# USB.net
KiCad netlist of a schematic drawn in Altium Designer
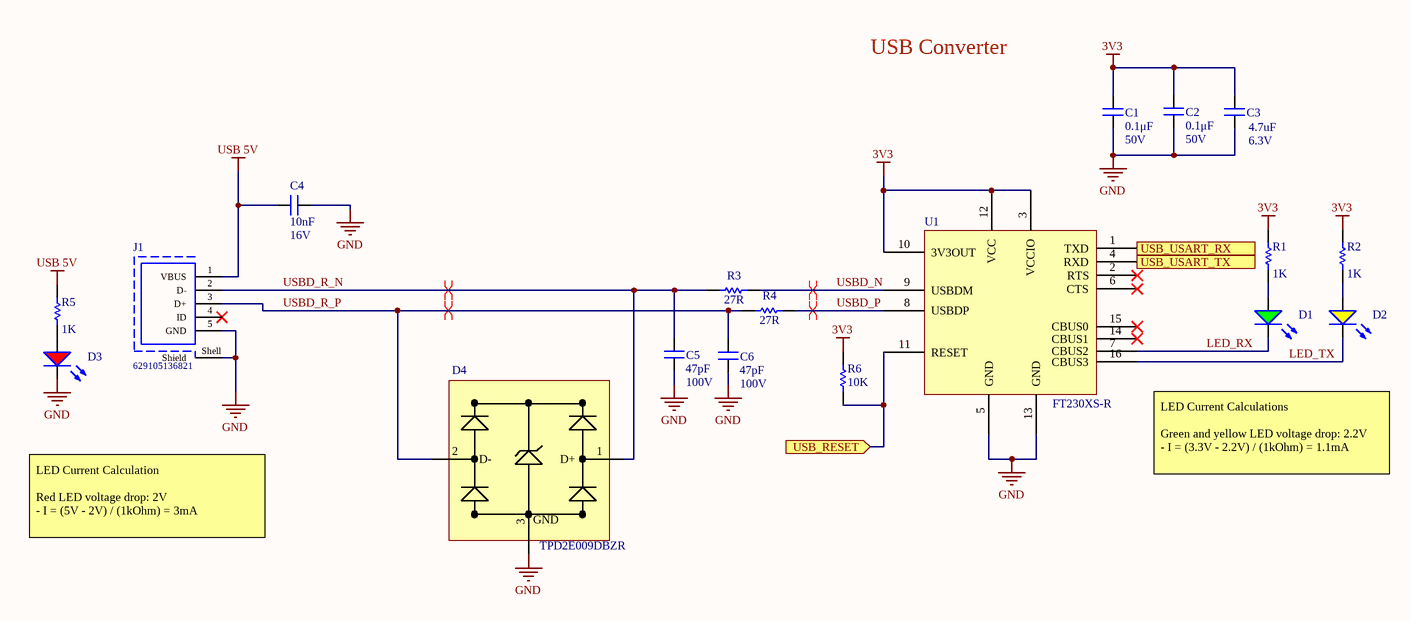
[diagram p0: USB.SchDoc]

(export (version "E")
  (design (tool "Eeschema 10.0.6"))
  (components
    (comp (ref "C1")
      (value "0.1μF")
      (footprint "CAP2012")
      (description "CAP CER 0.1UF 50V X7R 0805")
      (fields
        (field (name "TOLERANCE") "10%")
        (field (name "VOLTAGE RATING") "50V")
        (field (name "Comment") "CAP_0.1uF_50V_0805")
      )
      (libsource (lib "UWRT_Schematic_Library_2020") (part "CAP_0.1uF_50V_0805"))
    )
    (comp (ref "C2")
      (value "0.1μF")
      (footprint "CAP2012")
      (description "CAP CER 0.1UF 50V X7R 0805")
      (fields
        (field (name "TOLERANCE") "10%")
        (field (name "VOLTAGE RATING") "50V")
        (field (name "Comment") "CAP_0.1uF_50V_0805")
      )
      (libsource (lib "UWRT_Schematic_Library_2020") (part "CAP_0.1uF_50V_0805"))
    )
    (comp (ref "C3")
      (value "4.7uF")
      (footprint "CAPC0603(1608)55_N")
      (description "CAP CER 4.7UF 6.3V X5R 0603")
      (fields (field (name "VOLTAGE RATING") "6.3V") (field (name "Comment") "CAP_4.7uF_0603"))
      (libsource (lib "UWRT_Schematic_Library_2020") (part "CAP_4.7uF_0603"))
    )
    (comp (ref "C4")
      (value "10nF")
      (footprint "CAP0603")
      (description "CAP CER 10000PF 16V X7R 0603")
      (fields (field (name "VOLTAGE RATING") "16V") (field (name "Comment") "CAP_10nF_0603"))
      (libsource (lib "UWRT_Schematic_Library_2020") (part "CAP_10nF_0603"))
    )
    (comp (ref "C5")
      (value "47pF")
      (footprint "CAP0603")
      (description "CAP CER 47PF 100V C0G/NP0 0603")
      (fields (field (name "VOLTAGE RATING") "100V") (field (name "Comment") "CAP_47pF_100V_0603"))
      (libsource (lib "UWRT_Schematic_Library_2020") (part "CAP_47pF_100V_0603"))
    )
    (comp (ref "C6")
      (value "47pF")
      (footprint "CAP0603")
      (description "CAP CER 47PF 100V C0G/NP0 0603")
      (fields (field (name "VOLTAGE RATING") "100V") (field (name "Comment") "CAP_47pF_100V_0603"))
      (libsource (lib "UWRT_Schematic_Library_2020") (part "CAP_47pF_100V_0603"))
    )
    (comp (ref "D1")
      (value "LG R971-KN-1")
      (footprint "LED_0805_GREEN")
      (description "LED GREEN DIFFUSED 0805 SMD")
      (libsource (lib "UWRT_Schematic_Library_2020") (part "DIO_LED_G"))
    )
    (comp (ref "D2")
      (value "LY R976-PS-36")
      (footprint "LED_0805_YELLOW")
      (description "LED YELLOW DIFFUSED 0805 SMD")
      (libsource (lib "UWRT_Schematic_Library_2020") (part "DIO_LED_Y"))
    )
    (comp (ref "D3")
      (value "LS R976-NR-1")
      (footprint "LED_0805_RED")
      (description "LED RED DIFFUSED 0805 SMD")
      (libsource (lib "UWRT_Schematic_Library_2020") (part "DIO_LED_R"))
    )
    (comp (ref "D4")
      (value "TVS_DIODE_USB_5.5V")
      (footprint "SOT23-3")
      (description "TVS DIODE 5.5V 8V SOT23-3")
      (fields
        (field (name "MANUFACTURER") "Texas Instruments")
        (field (name "MANUFACTURER PART NUMBER") "TPD2E009DBZR")
      )
      (libsource (lib "UWRT_Schematic_Library_2020") (part "TVS_DIODE_USB_5.5V"))
    )
    (comp (ref "J1")
      (value "629105136821")
      (footprint "629105136821")
      (description "CONN RCPT USB2.0 MICRO B SMD R/A")
      (fields (field (name "MANUFACTURER") "Wurth Elektronik") (field (name "PUBLISHER") "WurthElektronik"))
      (libsource (lib "UWRT_Schematic_Library_2020") (part "WE 629105136821"))
    )
    (comp (ref "R1")
      (value "1K")
      (footprint "RESC0603(1608)_N")
      (description "RES SMD 1K OHM 5% 1/10W 0603")
      (fields (field (name "TOLERANCE") "5%") (field (name "Comment") "RES_1K_0603"))
      (libsource (lib "UWRT_Schematic_Library_2020") (part "RES_1K_0603"))
    )
    (comp (ref "R2")
      (value "1K")
      (footprint "RESC0603(1608)_N")
      (description "RES SMD 1K OHM 5% 1/10W 0603")
      (fields (field (name "TOLERANCE") "5%") (field (name "Comment") "RES_1K_0603"))
      (libsource (lib "UWRT_Schematic_Library_2020") (part "RES_1K_0603"))
    )
    (comp (ref "R3")
      (value "RES_27R_0603")
      (footprint "RESC0603(1608)_N")
      (description "RES SMD 27 OHM 5% 1/10W 0603")
      (fields
        (field (name "MANUFACTURER") "Yageo")
        (field (name "MANUFACTURER PART NUMBER") "RC0603JR-0727RL")
        (field (name "RESISTANCE") "27R")
      )
      (libsource (lib "UWRT_Schematic_Library_2020") (part "RES_27R_0603"))
    )
    (comp (ref "R4")
      (value "RES_27R_0603")
      (footprint "RESC0603(1608)_N")
      (description "RES SMD 27 OHM 5% 1/10W 0603")
      (fields
        (field (name "MANUFACTURER") "Yageo")
        (field (name "MANUFACTURER PART NUMBER") "RC0603JR-0727RL")
        (field (name "RESISTANCE") "27R")
      )
      (libsource (lib "UWRT_Schematic_Library_2020") (part "RES_27R_0603"))
    )
    (comp (ref "R5")
      (value "1K")
      (footprint "RESC0603(1608)_N")
      (description "RES SMD 1K OHM 5% 1/10W 0603")
      (fields (field (name "TOLERANCE") "5%") (field (name "Comment") "RES_1K_0603"))
      (libsource (lib "UWRT_Schematic_Library_2020") (part "RES_1K_0603"))
    )
    (comp (ref "R6")
      (value "10K")
      (footprint "RESC0603(1608)_N")
      (description "RES SMD 10K OHM 5% 1/10W 0603")
      (fields (field (name "TOLERANCE") "5%") (field (name "Comment") "RES_10K_0603"))
      (libsource (lib "UWRT_Schematic_Library_2020") (part "RES_10K_0603"))
    )
    (comp (ref "U1")
      (value "IC_USB_TRANSCEIVER")
      (footprint "SSOP16-0.635-5X4MM")
      (description "IC USB SERIAL BASIC UART 16SSOP")
      (fields (field (name "MANUFACTURER PART NUMBER 1") "FT230XS-R"))
      (libsource (lib "UWRT_Schematic_Library_2020") (part "IC_USB_TRANSCEIVER"))
    )
  )
  (nets
    (net (code "1") (name "/LED_RX") (class "Default")
      (node (ref "D1") (pin "2") (pinfunction "K_2") (pintype "passive"))
      (node (ref "U1") (pin "7") (pinfunction "CBUS2_7") (pintype "passive"))
    )
    (net (code "2") (name "/LED_TX") (class "Default")
      (node (ref "D2") (pin "2") (pinfunction "K_2") (pintype "passive"))
      (node (ref "U1") (pin "16") (pinfunction "CBUS3_16") (pintype "passive"))
    )
    (net (code "3") (name "/USBD_N") (class "Default")
      (node (ref "R3") (pin "2") (pinfunction "2_2") (pintype "passive"))
      (node (ref "U1") (pin "9") (pinfunction "USBDM_9") (pintype "passive"))
    )
    (net (code "4") (name "/USBD_P") (class "Default")
      (node (ref "R4") (pin "2") (pinfunction "2_2") (pintype "passive"))
      (node (ref "U1") (pin "8") (pinfunction "USBDP_8") (pintype "passive"))
    )
    (net (code "5") (name "/USBD_R_N") (class "Default")
      (node (ref "C5") (pin "2") (pinfunction "2_2") (pintype "passive"))
      (node (ref "D4") (pin "1") (pinfunction "D+_1") (pintype "passive"))
      (node (ref "J1") (pin "2") (pinfunction "D-_2") (pintype "passive"))
      (node (ref "R3") (pin "1") (pinfunction "1_1") (pintype "passive"))
    )
    (net (code "6") (name "/USBD_R_P") (class "Default")
      (node (ref "C6") (pin "1") (pinfunction "1_1") (pintype "passive"))
      (node (ref "D4") (pin "2") (pinfunction "D-_2") (pintype "passive"))
      (node (ref "J1") (pin "3") (pinfunction "D+_3") (pintype "passive"))
      (node (ref "R4") (pin "1") (pinfunction "1_1") (pintype "passive"))
    )
    (net (code "7") (name "/USB_RESET") (class "Default")
      (node (ref "R6") (pin "1") (pinfunction "1_1") (pintype "passive"))
      (node (ref "U1") (pin "11") (pinfunction "RESET_11") (pintype "passive"))
    )
    (net (code "8") (name "/USB_USART_RX") (class "Default")
      (node (ref "U1") (pin "1") (pinfunction "TXD_1") (pintype "passive"))
    )
    (net (code "9") (name "/USB_USART_TX") (class "Default")
      (node (ref "U1") (pin "4") (pinfunction "RXD_4") (pintype "passive"))
    )
    (net (code "10") (name "3V3") (class "Default")
      (node (ref "C1") (pin "2") (pinfunction "2_2") (pintype "passive"))
      (node (ref "C2") (pin "2") (pinfunction "2_2") (pintype "passive"))
      (node (ref "C3") (pin "1") (pinfunction "1_1") (pintype "passive"))
      (node (ref "R1") (pin "2") (pinfunction "2_2") (pintype "passive"))
      (node (ref "R2") (pin "2") (pinfunction "2_2") (pintype "passive"))
      (node (ref "R6") (pin "2") (pinfunction "2_2") (pintype "passive"))
      (node (ref "U1") (pin "10") (pinfunction "3V3OUT_10") (pintype "passive"))
      (node (ref "U1") (pin "12") (pinfunction "VCC_12") (pintype "passive"))
      (node (ref "U1") (pin "3") (pinfunction "VCCIO_3") (pintype "passive"))
    )
    (net (code "11") (name "GND") (class "Default")
      (node (ref "C1") (pin "1") (pinfunction "1_1") (pintype "passive"))
      (node (ref "C2") (pin "1") (pinfunction "1_1") (pintype "passive"))
      (node (ref "C3") (pin "2") (pinfunction "2_2") (pintype "passive"))
      (node (ref "C4") (pin "2") (pinfunction "2_2") (pintype "passive"))
      (node (ref "C5") (pin "1") (pinfunction "1_1") (pintype "passive"))
      (node (ref "C6") (pin "2") (pinfunction "2_2") (pintype "passive"))
      (node (ref "D3") (pin "2") (pinfunction "K_2") (pintype "passive"))
      (node (ref "D4") (pin "3") (pinfunction "GND_3") (pintype "passive"))
      (node (ref "J1") (pin "5") (pinfunction "GND_5") (pintype "passive"))
      (node (ref "J1") (pin "Shell") (pinfunction "Shield_Shell") (pintype "passive"))
      (node (ref "U1") (pin "13") (pinfunction "GND_13") (pintype "passive"))
      (node (ref "U1") (pin "5") (pinfunction "GND_5") (pintype "passive"))
    )
    (net (code "12") (name "Net-(D1-A)") (class "Default")
      (node (ref "D1") (pin "1") (pinfunction "A_1") (pintype "passive"))
      (node (ref "R1") (pin "1") (pinfunction "1_1") (pintype "passive"))
    )
    (net (code "13") (name "Net-(D2-A)") (class "Default")
      (node (ref "D2") (pin "1") (pinfunction "A_1") (pintype "passive"))
      (node (ref "R2") (pin "1") (pinfunction "1_1") (pintype "passive"))
    )
    (net (code "14") (name "Net-(D3-A)") (class "Default")
      (node (ref "D3") (pin "1") (pinfunction "A_1") (pintype "passive"))
      (node (ref "R5") (pin "1") (pinfunction "1_1") (pintype "passive"))
    )
    (net (code "15") (name "USB 5V") (class "Default")
      (node (ref "C4") (pin "1") (pinfunction "1_1") (pintype "passive"))
      (node (ref "J1") (pin "1") (pinfunction "VBUS_1") (pintype "passive"))
      (node (ref "R5") (pin "2") (pinfunction "2_2") (pintype "passive"))
    )
    (net (code "16") (name "unconnected-(J1-ID-Pad4)") (class "Default")
      (node (ref "J1") (pin "4") (pinfunction "ID_4") (pintype "passive+no_connect"))
    )
    (net (code "17") (name "unconnected-(U1-CBUS0-Pad15)") (class "Default")
      (node (ref "U1") (pin "15") (pinfunction "CBUS0_15") (pintype "passive+no_connect"))
    )
    (net (code "18") (name "unconnected-(U1-CBUS1-Pad14)") (class "Default")
      (node (ref "U1") (pin "14") (pinfunction "CBUS1_14") (pintype "passive+no_connect"))
    )
    (net (code "19") (name "unconnected-(U1-CTS-Pad6)") (class "Default")
      (node (ref "U1") (pin "6") (pinfunction "CTS_6") (pintype "passive+no_connect"))
    )
    (net (code "20") (name "unconnected-(U1-RTS-Pad2)") (class "Default")
      (node (ref "U1") (pin "2") (pinfunction "RTS_2") (pintype "passive+no_connect"))
    )
  )
)
